# TwirrePDB.net
KiCad netlist of a schematic drawn in EAGLE
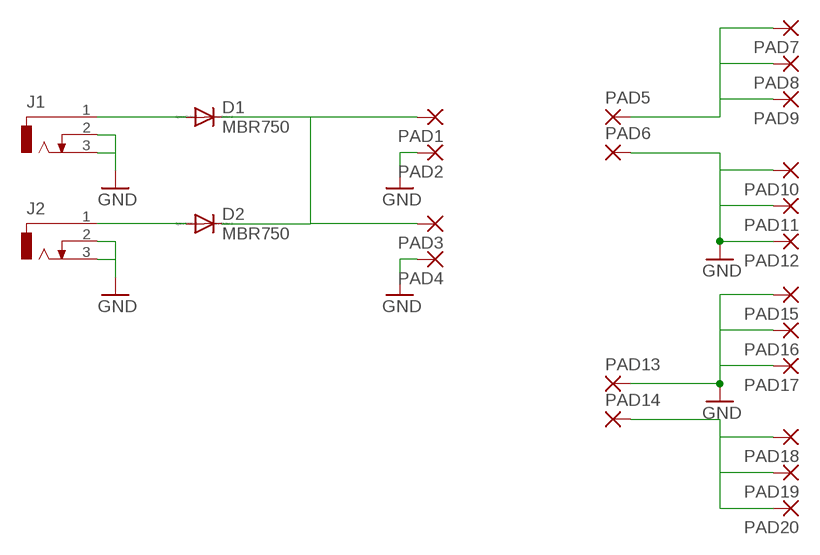
[diagram p0: schematic, sheet 1]

(export (version "E")
  (design (tool "Eeschema 10.0.6"))
  (components
    (comp (ref "D1")
      (value "MBR750")
      (footprint "eagle-import:TO220AC")
      (libsource (lib "eagle-import") (part "MBR750"))
    )
    (comp (ref "D2")
      (value "MBR750")
      (footprint "eagle-import:TO220AC")
      (libsource (lib "eagle-import") (part "MBR750"))
    )
    (comp (ref "J1")
      (value "DCJ0303")
      (footprint "eagle-import:DCJ0303")
      (libsource (lib "eagle-import") (part "DCJ0303"))
    )
    (comp (ref "J2")
      (value "DCJ0303")
      (footprint "eagle-import:DCJ0303")
      (libsource (lib "eagle-import") (part "DCJ0303"))
    )
    (comp (ref "PAD1")
      (value "2,54/0,9")
      (footprint "eagle-import:2,54_0,9")
      (libsource (lib "eagle-import") (part "2,54/0,9"))
    )
    (comp (ref "PAD2")
      (value "2,54/0,9")
      (footprint "eagle-import:2,54_0,9")
      (libsource (lib "eagle-import") (part "2,54/0,9"))
    )
    (comp (ref "PAD3")
      (value "2,54/0,9")
      (footprint "eagle-import:2,54_0,9")
      (libsource (lib "eagle-import") (part "2,54/0,9"))
    )
    (comp (ref "PAD4")
      (value "2,54/0,9")
      (footprint "eagle-import:2,54_0,9")
      (libsource (lib "eagle-import") (part "2,54/0,9"))
    )
    (comp (ref "PAD5")
      (value "2,54/0,9")
      (footprint "eagle-import:2,54_0,9")
      (libsource (lib "eagle-import") (part "2,54/0,9"))
    )
    (comp (ref "PAD6")
      (value "2,54/0,9")
      (footprint "eagle-import:2,54_0,9")
      (libsource (lib "eagle-import") (part "2,54/0,9"))
    )
    (comp (ref "PAD7")
      (value "2,54/0,9")
      (footprint "eagle-import:2,54_0,9")
      (libsource (lib "eagle-import") (part "2,54/0,9"))
    )
    (comp (ref "PAD8")
      (value "2,54/0,9")
      (footprint "eagle-import:2,54_0,9")
      (libsource (lib "eagle-import") (part "2,54/0,9"))
    )
    (comp (ref "PAD9")
      (value "2,54/0,9")
      (footprint "eagle-import:2,54_0,9")
      (libsource (lib "eagle-import") (part "2,54/0,9"))
    )
    (comp (ref "PAD10")
      (value "2,54/0,9")
      (footprint "eagle-import:2,54_0,9")
      (libsource (lib "eagle-import") (part "2,54/0,9"))
    )
    (comp (ref "PAD11")
      (value "2,54/0,9")
      (footprint "eagle-import:2,54_0,9")
      (libsource (lib "eagle-import") (part "2,54/0,9"))
    )
    (comp (ref "PAD12")
      (value "2,54/0,9")
      (footprint "eagle-import:2,54_0,9")
      (libsource (lib "eagle-import") (part "2,54/0,9"))
    )
    (comp (ref "PAD13")
      (value "2,54/0,9")
      (footprint "eagle-import:2,54_0,9")
      (libsource (lib "eagle-import") (part "2,54/0,9"))
    )
    (comp (ref "PAD14")
      (value "2,54/0,9")
      (footprint "eagle-import:2,54_0,9")
      (libsource (lib "eagle-import") (part "2,54/0,9"))
    )
    (comp (ref "PAD15")
      (value "2,54/0,9")
      (footprint "eagle-import:2,54_0,9")
      (libsource (lib "eagle-import") (part "2,54/0,9"))
    )
    (comp (ref "PAD16")
      (value "2,54/0,9")
      (footprint "eagle-import:2,54_0,9")
      (libsource (lib "eagle-import") (part "2,54/0,9"))
    )
    (comp (ref "PAD17")
      (value "2,54/0,9")
      (footprint "eagle-import:2,54_0,9")
      (libsource (lib "eagle-import") (part "2,54/0,9"))
    )
    (comp (ref "PAD18")
      (value "2,54/0,9")
      (footprint "eagle-import:2,54_0,9")
      (libsource (lib "eagle-import") (part "2,54/0,9"))
    )
    (comp (ref "PAD19")
      (value "2,54/0,9")
      (footprint "eagle-import:2,54_0,9")
      (libsource (lib "eagle-import") (part "2,54/0,9"))
    )
    (comp (ref "PAD20")
      (value "2,54/0,9")
      (footprint "eagle-import:2,54_0,9")
      (libsource (lib "eagle-import") (part "2,54/0,9"))
    )
  )
  (nets
    (net (code "1") (name "GND") (class "Default")
      (node (ref "J1") (pin "2") (pinfunction "2_2") (pintype "passive"))
      (node (ref "J1") (pin "3") (pinfunction "3_3") (pintype "passive"))
      (node (ref "J2") (pin "2") (pinfunction "2_2") (pintype "passive"))
      (node (ref "J2") (pin "3") (pinfunction "3_3") (pintype "passive"))
      (node (ref "PAD10") (pin "1") (pinfunction "P_1") (pintype "passive"))
      (node (ref "PAD11") (pin "1") (pinfunction "P_1") (pintype "passive"))
      (node (ref "PAD12") (pin "1") (pinfunction "P_1") (pintype "passive"))
      (node (ref "PAD13") (pin "1") (pinfunction "P_1") (pintype "passive"))
      (node (ref "PAD15") (pin "1") (pinfunction "P_1") (pintype "passive"))
      (node (ref "PAD16") (pin "1") (pinfunction "P_1") (pintype "passive"))
      (node (ref "PAD17") (pin "1") (pinfunction "P_1") (pintype "passive"))
      (node (ref "PAD2") (pin "1") (pinfunction "P_1") (pintype "passive"))
      (node (ref "PAD4") (pin "1") (pinfunction "P_1") (pintype "passive"))
      (node (ref "PAD6") (pin "1") (pinfunction "P_1") (pintype "passive"))
    )
    (net (code "2") (name "Net-(D1-PadA)") (class "Default")
      (node (ref "D1") (pin "A") (pinfunction "A_A") (pintype "passive"))
      (node (ref "J1") (pin "1") (pinfunction "1_1") (pintype "passive"))
    )
    (net (code "3") (name "Net-(D2-PadA)") (class "Default")
      (node (ref "D2") (pin "A") (pinfunction "A_A") (pintype "passive"))
      (node (ref "J2") (pin "1") (pinfunction "1_1") (pintype "passive"))
    )
    (net (code "4") (name "Net-(PAD1-P)") (class "Default")
      (node (ref "D1") (pin "C") (pinfunction "C_C") (pintype "passive"))
      (node (ref "D2") (pin "C") (pinfunction "C_C") (pintype "passive"))
      (node (ref "PAD1") (pin "1") (pinfunction "P_1") (pintype "passive"))
      (node (ref "PAD3") (pin "1") (pinfunction "P_1") (pintype "passive"))
    )
    (net (code "5") (name "Net-(PAD5-P)") (class "Default")
      (node (ref "PAD5") (pin "1") (pinfunction "P_1") (pintype "passive"))
      (node (ref "PAD7") (pin "1") (pinfunction "P_1") (pintype "passive"))
      (node (ref "PAD8") (pin "1") (pinfunction "P_1") (pintype "passive"))
      (node (ref "PAD9") (pin "1") (pinfunction "P_1") (pintype "passive"))
    )
    (net (code "6") (name "Net-(PAD14-P)") (class "Default")
      (node (ref "PAD14") (pin "1") (pinfunction "P_1") (pintype "passive"))
      (node (ref "PAD18") (pin "1") (pinfunction "P_1") (pintype "passive"))
      (node (ref "PAD19") (pin "1") (pinfunction "P_1") (pintype "passive"))
      (node (ref "PAD20") (pin "1") (pinfunction "P_1") (pintype "passive"))
    )
  )
)
